# uv-dosimeter-featherwing-mk-1_2.net
KiCad netlist of a schematic drawn in EAGLE
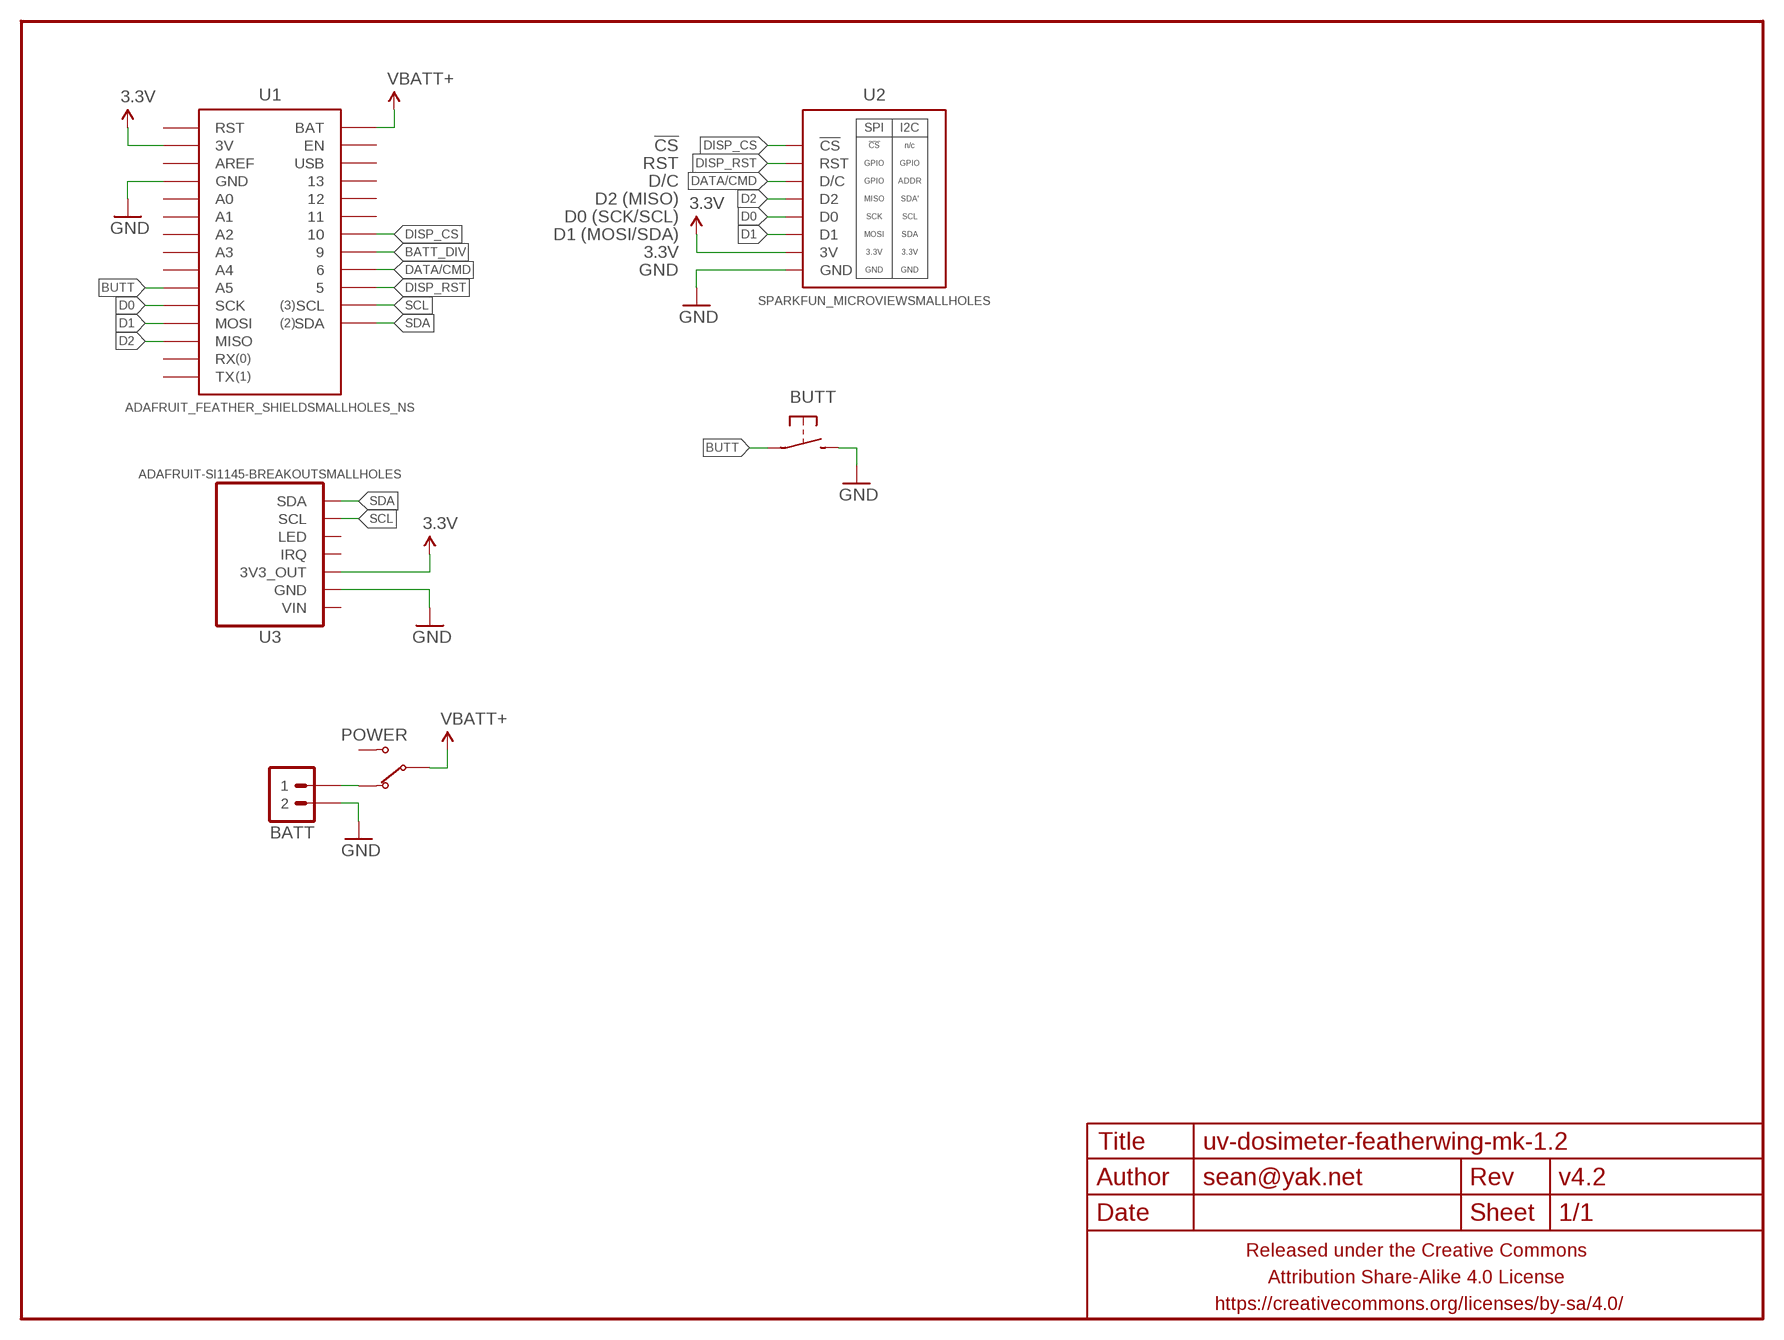
[diagram p0: schematic, sheet 1]

(export (version "E")
  (design (tool "Eeschema 10.0.6"))
  (components
    (comp (ref "BATT")
      (value "M02JST-2MM-SMT")
      (footprint "eagle-import:JST-2-SMD")
      (libsource (lib "eagle-import") (part "M02JST-2MM-SMT"))
    )
    (comp (ref "BUTT")
      (value "SPST-NO-TACT3MM-PTH-SMALL-PADS")
      (footprint "eagle-import:DTS-3-SMALL-PADS")
      (libsource (lib "eagle-import") (part "SPST-NO-TACT3MM-PTH-SMALL-PADS"))
    )
    (comp (ref "FRAME1")
      (value "FRAME-LETTERNO_PACKAGE")
      (footprint "eagle-import:DUMMY")
      (fields (field (name "DESIGNER") "sean@yak.net") (field (name "VERSION") "v4.2"))
      (libsource (lib "eagle-import") (part "FRAME-LETTERNO_PACKAGE"))
    )
    (comp (ref "POWER")
      (value "SWITCH-SPDTPTH-VERT-2.54MM")
      (footprint "eagle-import:SWITCH-SPDT")
      (libsource (lib "eagle-import") (part "SWITCH-SPDTPTH-VERT-2.54MM"))
    )
    (comp (ref "U1")
      (value "ADAFRUIT_FEATHER_SHIELDSMALLHOLES_NS")
      (footprint "eagle-import:ADAFRUIT_FEATHER_SMALLHOLES_NS")
      (libsource (lib "eagle-import") (part "ADAFRUIT_FEATHER_SHIELDSMALLHOLES_NS"))
    )
    (comp (ref "U2")
      (value "SPARKFUN_MICROVIEWSMALLHOLES")
      (footprint "eagle-import:SPARKFUN-MICROVIEW-SMALLHOLES")
      (libsource (lib "eagle-import") (part "SPARKFUN_MICROVIEWSMALLHOLES"))
    )
    (comp (ref "U3")
      (value "ADAFRUIT-SI1145-BREAKOUTSMALLHOLES")
      (footprint "eagle-import:ADAFRUIT-SI1145-BREAKOUT-LESSSILK-SMALLHOLES")
      (libsource (lib "eagle-import") (part "ADAFRUIT-SI1145-BREAKOUTSMALLHOLES"))
    )
  )
  (nets
    (net (code "1") (name "3.3V") (class "Default")
      (node (ref "U1") (pin "3V") (pinfunction "3V_3V") (pintype "bidirectional"))
      (node (ref "U2") (pin "3V") (pinfunction "3V_3V") (pintype "bidirectional"))
      (node (ref "U3") (pin "3V3_OUT") (pinfunction "3V3_OUT_3V3_OUT") (pintype "passive"))
    )
    (net (code "2") (name "BATT_DIV") (class "Default")
      (node (ref "U1") (pin "9") (pinfunction "9_9") (pintype "bidirectional"))
    )
    (net (code "3") (name "BUTT") (class "Default")
      (node (ref "BUTT") (pin "1") (pinfunction "1_1") (pintype "passive"))
      (node (ref "U1") (pin "A5") (pinfunction "A5_A5") (pintype "bidirectional"))
    )
    (net (code "4") (name "D0") (class "Default")
      (node (ref "U1") (pin "SCK") (pinfunction "SCK_SCK") (pintype "bidirectional"))
      (node (ref "U2") (pin "D0") (pinfunction "D0_D0") (pintype "bidirectional"))
    )
    (net (code "5") (name "D1") (class "Default")
      (node (ref "U1") (pin "MOSI") (pinfunction "MOSI_MOSI") (pintype "bidirectional"))
      (node (ref "U2") (pin "D1") (pinfunction "D1_D1") (pintype "bidirectional"))
    )
    (net (code "6") (name "D2") (class "Default")
      (node (ref "U1") (pin "MISO") (pinfunction "MISO_MISO") (pintype "bidirectional"))
      (node (ref "U2") (pin "D2") (pinfunction "D2_D2") (pintype "bidirectional"))
    )
    (net (code "7") (name "DATA{slash}CMD") (class "Default")
      (node (ref "U1") (pin "6") (pinfunction "6_6") (pintype "bidirectional"))
      (node (ref "U2") (pin "D/C") (pinfunction "D/C_D/C") (pintype "bidirectional"))
    )
    (net (code "8") (name "DISP_CS") (class "Default")
      (node (ref "U1") (pin "10") (pinfunction "10_10") (pintype "bidirectional"))
      (node (ref "U2") (pin "CS") (pinfunction "~{CS}_CS") (pintype "bidirectional"))
    )
    (net (code "9") (name "DISP_RST") (class "Default")
      (node (ref "U1") (pin "5") (pinfunction "5_5") (pintype "bidirectional"))
      (node (ref "U2") (pin "RST") (pinfunction "RST_RST") (pintype "bidirectional"))
    )
    (net (code "10") (name "GND") (class "Default")
      (node (ref "BATT") (pin "1") (pinfunction "2_1") (pintype "passive"))
      (node (ref "BUTT") (pin "2") (pinfunction "2_2") (pintype "passive"))
      (node (ref "U1") (pin "GND@0") (pinfunction "GND_GND@0") (pintype "bidirectional"))
      (node (ref "U1") (pin "GND@1") (pinfunction "GND_GND@1") (pintype "bidirectional"))
      (node (ref "U2") (pin "GND") (pinfunction "GND_GND") (pintype "bidirectional"))
      (node (ref "U3") (pin "GND") (pinfunction "GND_GND") (pintype "passive"))
    )
    (net (code "11") (name "Net-(BATT-1)") (class "Default")
      (node (ref "BATT") (pin "2") (pinfunction "1_2") (pintype "passive"))
      (node (ref "POWER") (pin "1") (pinfunction "NC_1") (pintype "passive"))
    )
    (net (code "12") (name "SCL") (class "Default")
      (node (ref "U1") (pin "SCL") (pinfunction "SCL_SCL") (pintype "bidirectional"))
      (node (ref "U3") (pin "SCL") (pinfunction "SCL_SCL") (pintype "passive"))
    )
    (net (code "13") (name "SDA") (class "Default")
      (node (ref "U1") (pin "SDA") (pinfunction "SDA_SDA") (pintype "bidirectional"))
      (node (ref "U3") (pin "SDA") (pinfunction "SDA_SDA") (pintype "passive"))
    )
    (net (code "14") (name "VBATT+") (class "Default")
      (node (ref "POWER") (pin "2") (pinfunction "COM_2") (pintype "passive"))
      (node (ref "U1") (pin "BAT") (pinfunction "BAT_BAT") (pintype "bidirectional"))
    )
    (net (code "15") (name "unconnected-(POWER-NO-Pad3)") (class "Default")
      (node (ref "POWER") (pin "3") (pinfunction "NO_3") (pintype "passive"))
    )
    (net (code "16") (name "unconnected-(U1-Pad11)") (class "Default")
      (node (ref "U1") (pin "11") (pinfunction "11_11") (pintype "bidirectional"))
    )
    (net (code "17") (name "unconnected-(U1-Pad12)") (class "Default")
      (node (ref "U1") (pin "12") (pinfunction "12_12") (pintype "bidirectional"))
    )
    (net (code "18") (name "unconnected-(U1-Pad13)") (class "Default")
      (node (ref "U1") (pin "13") (pinfunction "13_13") (pintype "bidirectional"))
    )
    (net (code "19") (name "unconnected-(U1-PadA0)") (class "Default")
      (node (ref "U1") (pin "A0") (pinfunction "A0_A0") (pintype "bidirectional"))
    )
    (net (code "20") (name "unconnected-(U1-PadA1)") (class "Default")
      (node (ref "U1") (pin "A1") (pinfunction "A1_A1") (pintype "bidirectional"))
    )
    (net (code "21") (name "unconnected-(U1-PadA2)") (class "Default")
      (node (ref "U1") (pin "A2") (pinfunction "A2_A2") (pintype "bidirectional"))
    )
    (net (code "22") (name "unconnected-(U1-PadA3)") (class "Default")
      (node (ref "U1") (pin "A3") (pinfunction "A3_A3") (pintype "bidirectional"))
    )
    (net (code "23") (name "unconnected-(U1-PadA4)") (class "Default")
      (node (ref "U1") (pin "A4") (pinfunction "A4_A4") (pintype "bidirectional"))
    )
    (net (code "24") (name "unconnected-(U1-PadAREF)") (class "Default")
      (node (ref "U1") (pin "AREF") (pinfunction "AREF_AREF") (pintype "bidirectional"))
    )
    (net (code "25") (name "unconnected-(U1-PadEN)") (class "Default")
      (node (ref "U1") (pin "EN") (pinfunction "EN_EN") (pintype "bidirectional"))
    )
    (net (code "26") (name "unconnected-(U1-PadRST)") (class "Default")
      (node (ref "U1") (pin "RST") (pinfunction "RST_RST") (pintype "bidirectional"))
    )
    (net (code "27") (name "unconnected-(U1-PadRX)") (class "Default")
      (node (ref "U1") (pin "RX") (pinfunction "RX_RX") (pintype "bidirectional"))
    )
    (net (code "28") (name "unconnected-(U1-PadTX)") (class "Default")
      (node (ref "U1") (pin "TX") (pinfunction "TX_TX") (pintype "bidirectional"))
    )
    (net (code "29") (name "unconnected-(U1-PadUSB)") (class "Default")
      (node (ref "U1") (pin "USB") (pinfunction "USB_USB") (pintype "bidirectional"))
    )
    (net (code "30") (name "unconnected-(U3-PadIRQ)") (class "Default")
      (node (ref "U3") (pin "IRQ") (pinfunction "IRQ_IRQ") (pintype "passive"))
    )
    (net (code "31") (name "unconnected-(U3-PadLED)") (class "Default")
      (node (ref "U3") (pin "LED") (pinfunction "LED_LED") (pintype "passive"))
    )
    (net (code "32") (name "unconnected-(U3-PadVIN)") (class "Default")
      (node (ref "U3") (pin "VIN") (pinfunction "VIN_VIN") (pintype "passive"))
    )
  )
)
